# TinyTrackuino.net
KiCad netlist of a schematic drawn in EAGLE
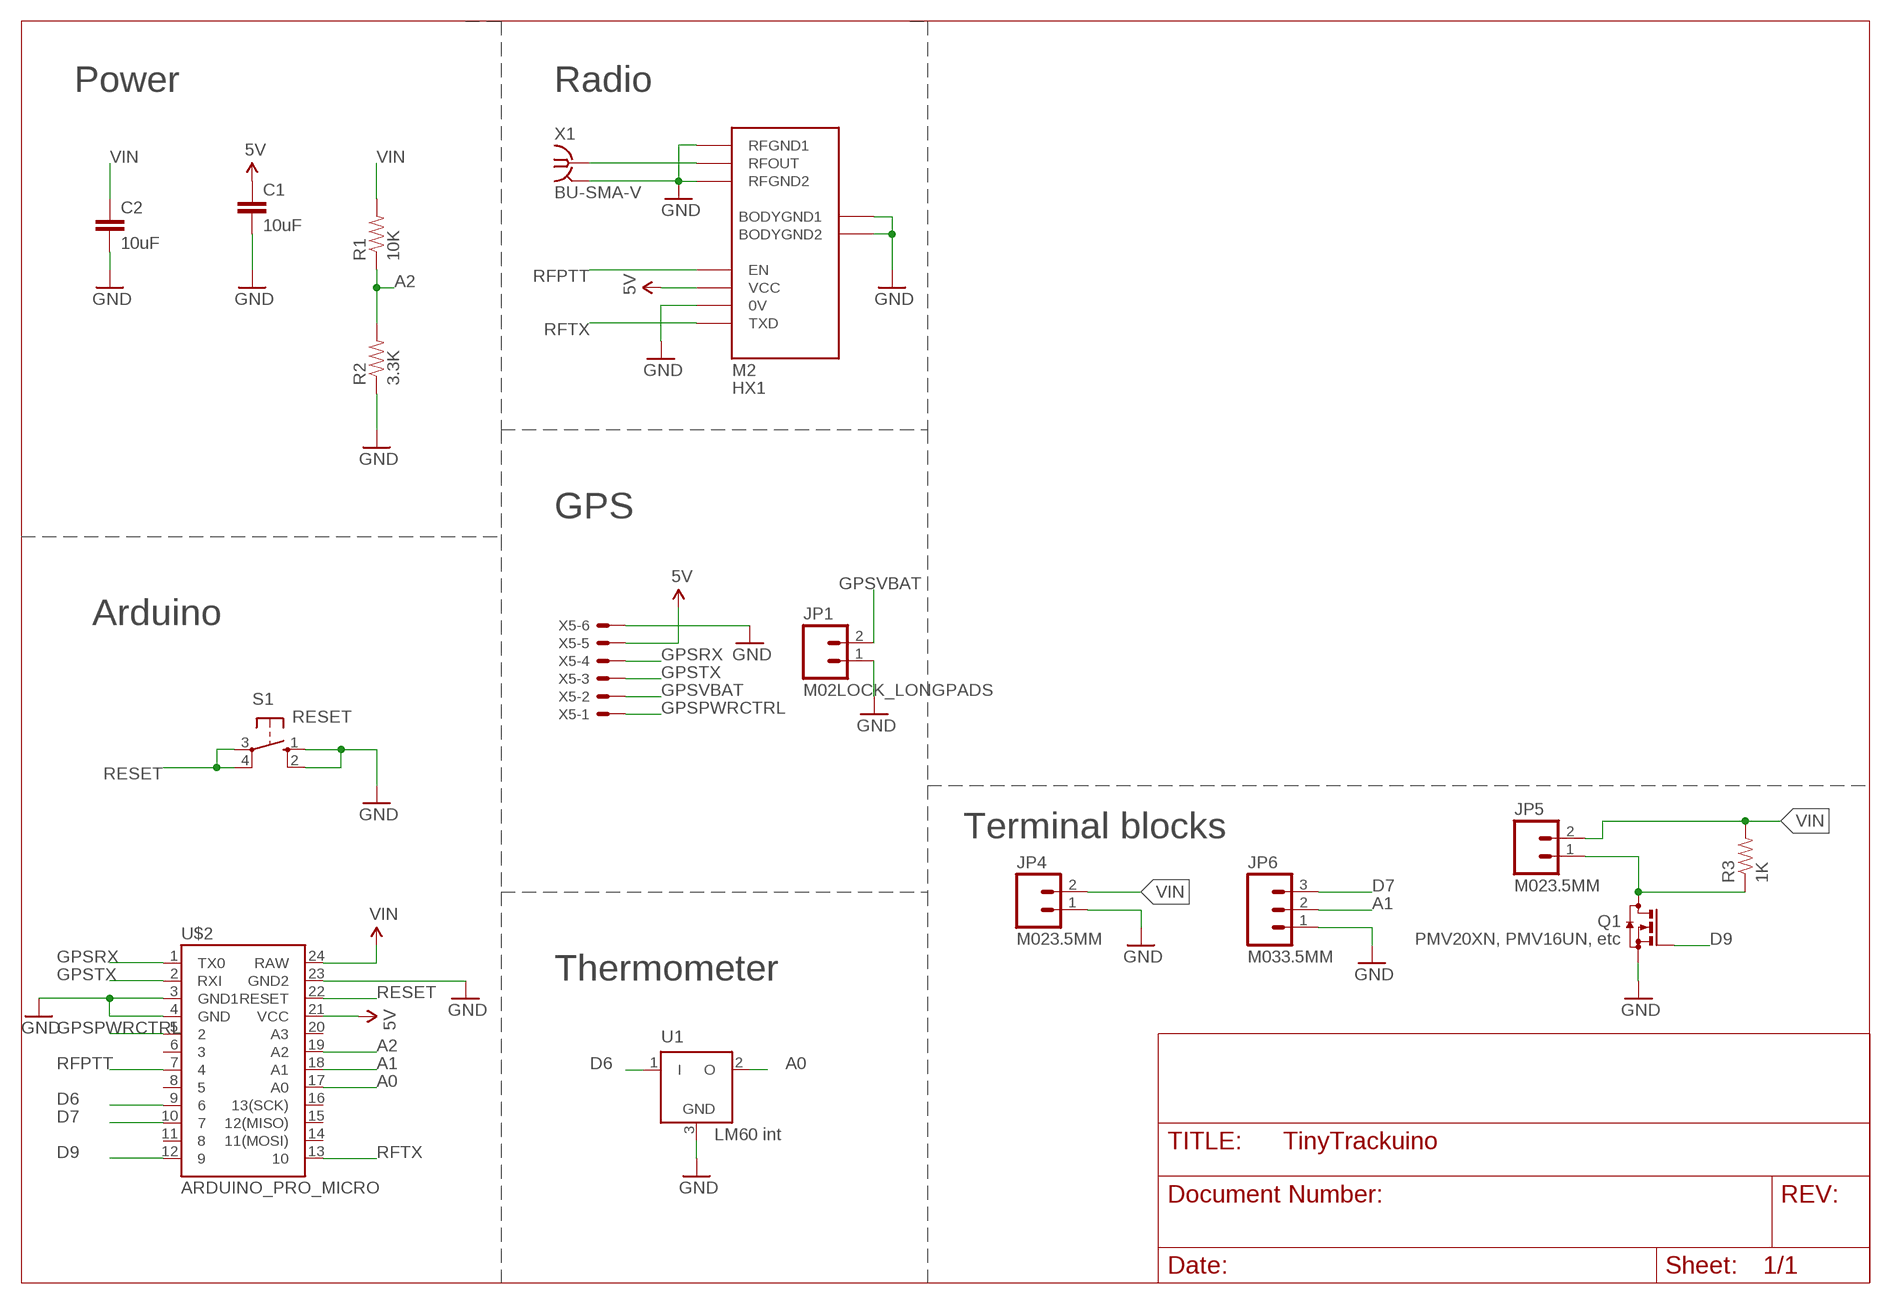
[diagram p0: schematic, sheet 1]

(export (version "E")
  (design (tool "Eeschema 10.0.6"))
  (components
    (comp (ref "C1")
      (value "10uF")
      (footprint "eagle-import:1206")
      (libsource (lib "eagle-import") (part "CAP1206"))
    )
    (comp (ref "C2")
      (value "10uF")
      (footprint "eagle-import:1206")
      (libsource (lib "eagle-import") (part "CAP1206"))
    )
    (comp (ref "JP1")
      (value "M02LOCK_LONGPADS")
      (footprint "eagle-import:1X02_LOCK_LONGPADS")
      (libsource (lib "eagle-import") (part "M02LOCK_LONGPADS"))
    )
    (comp (ref "JP4")
      (value "M023.5MM")
      (footprint "eagle-import:SCREWTERMINAL-3.5MM-2")
      (libsource (lib "eagle-import") (part "M023.5MM"))
    )
    (comp (ref "JP5")
      (value "M023.5MM")
      (footprint "eagle-import:SCREWTERMINAL-3.5MM-2")
      (libsource (lib "eagle-import") (part "M023.5MM"))
    )
    (comp (ref "JP6")
      (value "M033.5MM")
      (footprint "eagle-import:SCREWTERMINAL-3.5MM-3")
      (libsource (lib "eagle-import") (part "M03SCREW"))
    )
    (comp (ref "M2")
      (value "HX1")
      (footprint "eagle-import:HX1")
      (libsource (lib "eagle-import") (part "HX1"))
    )
    (comp (ref "Q1")
      (value "PMV20XN, PMV16UN, etc")
      (footprint "eagle-import:SOT23")
      (libsource (lib "eagle-import") (part "BSS123"))
    )
    (comp (ref "R1")
      (value "10K")
      (footprint "eagle-import:0603-RES")
      (libsource (lib "eagle-import") (part "RESISTOR0603-RES"))
    )
    (comp (ref "R2")
      (value "3.3K")
      (footprint "eagle-import:0603-RES")
      (libsource (lib "eagle-import") (part "RESISTOR0603-RES"))
    )
    (comp (ref "R3")
      (value "1K")
      (footprint "eagle-import:0603-RES")
      (libsource (lib "eagle-import") (part "RESISTOR0603-RES"))
    )
    (comp (ref "S1")
      (value "RESET")
      (footprint "eagle-import:B3F-10XX")
      (libsource (lib "eagle-import") (part "10-XX"))
    )
    (comp (ref "U$2")
      (value "ARDUINO_PRO_MICRO")
      (footprint "eagle-import:ARDUINO_PRO_MICRO")
      (libsource (lib "eagle-import") (part "ARDUINO_PRO_MICRO"))
    )
    (comp (ref "U1")
      (value "LM60 int")
      (footprint "eagle-import:TO92")
      (libsource (lib "eagle-import") (part "LM60"))
    )
    (comp (ref "X1")
      (value "BU-SMA-V")
      (footprint "eagle-import:BU-SMA-V")
      (libsource (lib "eagle-import") (part "BU-SMA-V"))
    )
    (comp (ref "X5")
      (value "SM06B-SRSS-TB")
      (footprint "eagle-import:SM06B-SRSS-TB")
      (libsource (lib "eagle-import") (part "?M06B-SRSS-TBS"))
    )
  )
  (nets
    (net (code "1") (name "/A0") (class "Default")
      (node (ref "U$2") (pin "17") (pinfunction "A0_17") (pintype "bidirectional"))
      (node (ref "U1") (pin "2") (pinfunction "O_2") (pintype "input"))
    )
    (net (code "2") (name "/A1") (class "Default")
      (node (ref "JP6") (pin "2") (pinfunction "2_2") (pintype "passive"))
      (node (ref "U$2") (pin "18") (pinfunction "A1_18") (pintype "bidirectional"))
    )
    (net (code "3") (name "/A2") (class "Default")
      (node (ref "R1") (pin "1") (pinfunction "1_1") (pintype "passive"))
      (node (ref "R2") (pin "2") (pinfunction "2_2") (pintype "passive"))
      (node (ref "U$2") (pin "19") (pinfunction "A2_19") (pintype "bidirectional"))
    )
    (net (code "4") (name "/D6") (class "Default")
      (node (ref "U$2") (pin "9") (pinfunction "6_9") (pintype "bidirectional"))
      (node (ref "U1") (pin "1") (pinfunction "I_1") (pintype "input"))
    )
    (net (code "5") (name "/D7") (class "Default")
      (node (ref "JP6") (pin "3") (pinfunction "3_3") (pintype "passive"))
      (node (ref "U$2") (pin "10") (pinfunction "7_10") (pintype "bidirectional"))
    )
    (net (code "6") (name "/D9") (class "Default")
      (node (ref "Q1") (pin "1") (pinfunction "G_1") (pintype "passive"))
      (node (ref "U$2") (pin "12") (pinfunction "9_12") (pintype "bidirectional"))
    )
    (net (code "7") (name "/GPSPWRCTRL") (class "Default")
      (node (ref "U$2") (pin "5") (pinfunction "2_5") (pintype "bidirectional"))
      (node (ref "X5") (pin "1") (pinfunction "S_1") (pintype "passive"))
    )
    (net (code "8") (name "/GPSRX") (class "Default")
      (node (ref "U$2") (pin "1") (pinfunction "TX0_1") (pintype "bidirectional"))
      (node (ref "X5") (pin "4") (pinfunction "S_4") (pintype "passive"))
    )
    (net (code "9") (name "/GPSTX") (class "Default")
      (node (ref "U$2") (pin "2") (pinfunction "RXI_2") (pintype "bidirectional"))
      (node (ref "X5") (pin "3") (pinfunction "S_3") (pintype "passive"))
    )
    (net (code "10") (name "/GPSVBAT") (class "Default")
      (node (ref "JP1") (pin "2") (pinfunction "2_2") (pintype "passive"))
      (node (ref "X5") (pin "2") (pinfunction "S_2") (pintype "passive"))
    )
    (net (code "11") (name "/RESET") (class "Default")
      (node (ref "S1") (pin "3") (pinfunction "P_3") (pintype "passive"))
      (node (ref "S1") (pin "4") (pinfunction "P1_4") (pintype "passive"))
      (node (ref "U$2") (pin "22") (pinfunction "RESET_22") (pintype "bidirectional"))
    )
    (net (code "12") (name "/RFPTT") (class "Default")
      (node (ref "M2") (pin "EN") (pinfunction "EN_EN") (pintype "bidirectional"))
      (node (ref "U$2") (pin "7") (pinfunction "4_7") (pintype "bidirectional"))
    )
    (net (code "13") (name "/RFTX") (class "Default")
      (node (ref "M2") (pin "TXD") (pinfunction "TXD_TXD") (pintype "bidirectional"))
      (node (ref "U$2") (pin "13") (pinfunction "10_13") (pintype "bidirectional"))
    )
    (net (code "14") (name "5V") (class "Default")
      (node (ref "C1") (pin "1") (pinfunction "1_1") (pintype "passive"))
      (node (ref "M2") (pin "VCC") (pinfunction "VCC_VCC") (pintype "bidirectional"))
      (node (ref "U$2") (pin "21") (pinfunction "VCC_21") (pintype "bidirectional"))
      (node (ref "X5") (pin "5") (pinfunction "S_5") (pintype "passive"))
    )
    (net (code "15") (name "GND") (class "Default")
      (node (ref "C1") (pin "2") (pinfunction "2_2") (pintype "passive"))
      (node (ref "C2") (pin "2") (pinfunction "2_2") (pintype "passive"))
      (node (ref "JP1") (pin "1") (pinfunction "1_1") (pintype "passive"))
      (node (ref "JP4") (pin "1") (pinfunction "1_1") (pintype "passive"))
      (node (ref "JP6") (pin "1") (pinfunction "1_1") (pintype "passive"))
      (node (ref "M2") (pin "0V") (pinfunction "0V_0V") (pintype "bidirectional"))
      (node (ref "M2") (pin "BODYGND1") (pinfunction "BODYGND1_BODYGND1") (pintype "bidirectional"))
      (node (ref "M2") (pin "BODYGND2") (pinfunction "BODYGND2_BODYGND2") (pintype "bidirectional"))
      (node (ref "M2") (pin "RFGND1") (pinfunction "RFGND1_RFGND1") (pintype "bidirectional"))
      (node (ref "M2") (pin "RFGND2") (pinfunction "RFGND2_RFGND2") (pintype "bidirectional"))
      (node (ref "Q1") (pin "2") (pinfunction "S_2") (pintype "passive"))
      (node (ref "R2") (pin "1") (pinfunction "1_1") (pintype "passive"))
      (node (ref "S1") (pin "1") (pinfunction "S_1") (pintype "passive"))
      (node (ref "S1") (pin "2") (pinfunction "S1_2") (pintype "passive"))
      (node (ref "U$2") (pin "23") (pinfunction "GND2_23") (pintype "bidirectional"))
      (node (ref "U$2") (pin "3") (pinfunction "GND1_3") (pintype "bidirectional"))
      (node (ref "U$2") (pin "4") (pinfunction "GND_4") (pintype "bidirectional"))
      (node (ref "U1") (pin "3") (pinfunction "GND_3") (pintype "power_in"))
      (node (ref "X1") (pin "2") (pinfunction "GND_2") (pintype "power_in"))
      (node (ref "X5") (pin "6") (pinfunction "S_6") (pintype "passive"))
    )
    (net (code "16") (name "Net-(M2-PadRFOUT)") (class "Default")
      (node (ref "M2") (pin "RFOUT") (pinfunction "RFOUT_RFOUT") (pintype "bidirectional"))
      (node (ref "X1") (pin "1") (pinfunction "1_1") (pintype "passive"))
    )
    (net (code "17") (name "Net-(Q1-D)") (class "Default")
      (node (ref "JP5") (pin "1") (pinfunction "1_1") (pintype "passive"))
      (node (ref "Q1") (pin "3") (pinfunction "D_3") (pintype "passive"))
      (node (ref "R3") (pin "1") (pinfunction "1_1") (pintype "passive"))
    )
    (net (code "18") (name "VIN") (class "Default")
      (node (ref "C2") (pin "1") (pinfunction "1_1") (pintype "passive"))
      (node (ref "JP4") (pin "2") (pinfunction "2_2") (pintype "passive"))
      (node (ref "JP5") (pin "2") (pinfunction "2_2") (pintype "passive"))
      (node (ref "R1") (pin "2") (pinfunction "2_2") (pintype "passive"))
      (node (ref "R3") (pin "2") (pinfunction "2_2") (pintype "passive"))
      (node (ref "U$2") (pin "24") (pinfunction "RAW_24") (pintype "bidirectional"))
    )
    (net (code "19") (name "unconnected-(U$2-3-Pad6)") (class "Default")
      (node (ref "U$2") (pin "6") (pinfunction "3_6") (pintype "bidirectional"))
    )
    (net (code "20") (name "unconnected-(U$2-5-Pad8)") (class "Default")
      (node (ref "U$2") (pin "8") (pinfunction "5_8") (pintype "bidirectional"))
    )
    (net (code "21") (name "unconnected-(U$2-8-Pad11)") (class "Default")
      (node (ref "U$2") (pin "11") (pinfunction "8_11") (pintype "bidirectional"))
    )
    (net (code "22") (name "unconnected-(U$2-11(MOSI)-Pad14)") (class "Default")
      (node (ref "U$2") (pin "14") (pinfunction "11(MOSI)_14") (pintype "bidirectional"))
    )
    (net (code "23") (name "unconnected-(U$2-12(MISO)-Pad15)") (class "Default")
      (node (ref "U$2") (pin "15") (pinfunction "12(MISO)_15") (pintype "bidirectional"))
    )
    (net (code "24") (name "unconnected-(U$2-13(SCK)-Pad16)") (class "Default")
      (node (ref "U$2") (pin "16") (pinfunction "13(SCK)_16") (pintype "bidirectional"))
    )
    (net (code "25") (name "unconnected-(U$2-A3-Pad20)") (class "Default")
      (node (ref "U$2") (pin "20") (pinfunction "A3_20") (pintype "bidirectional"))
    )
  )
)
